# solar-pmic.net
KiCad netlist of a schematic drawn in EAGLE
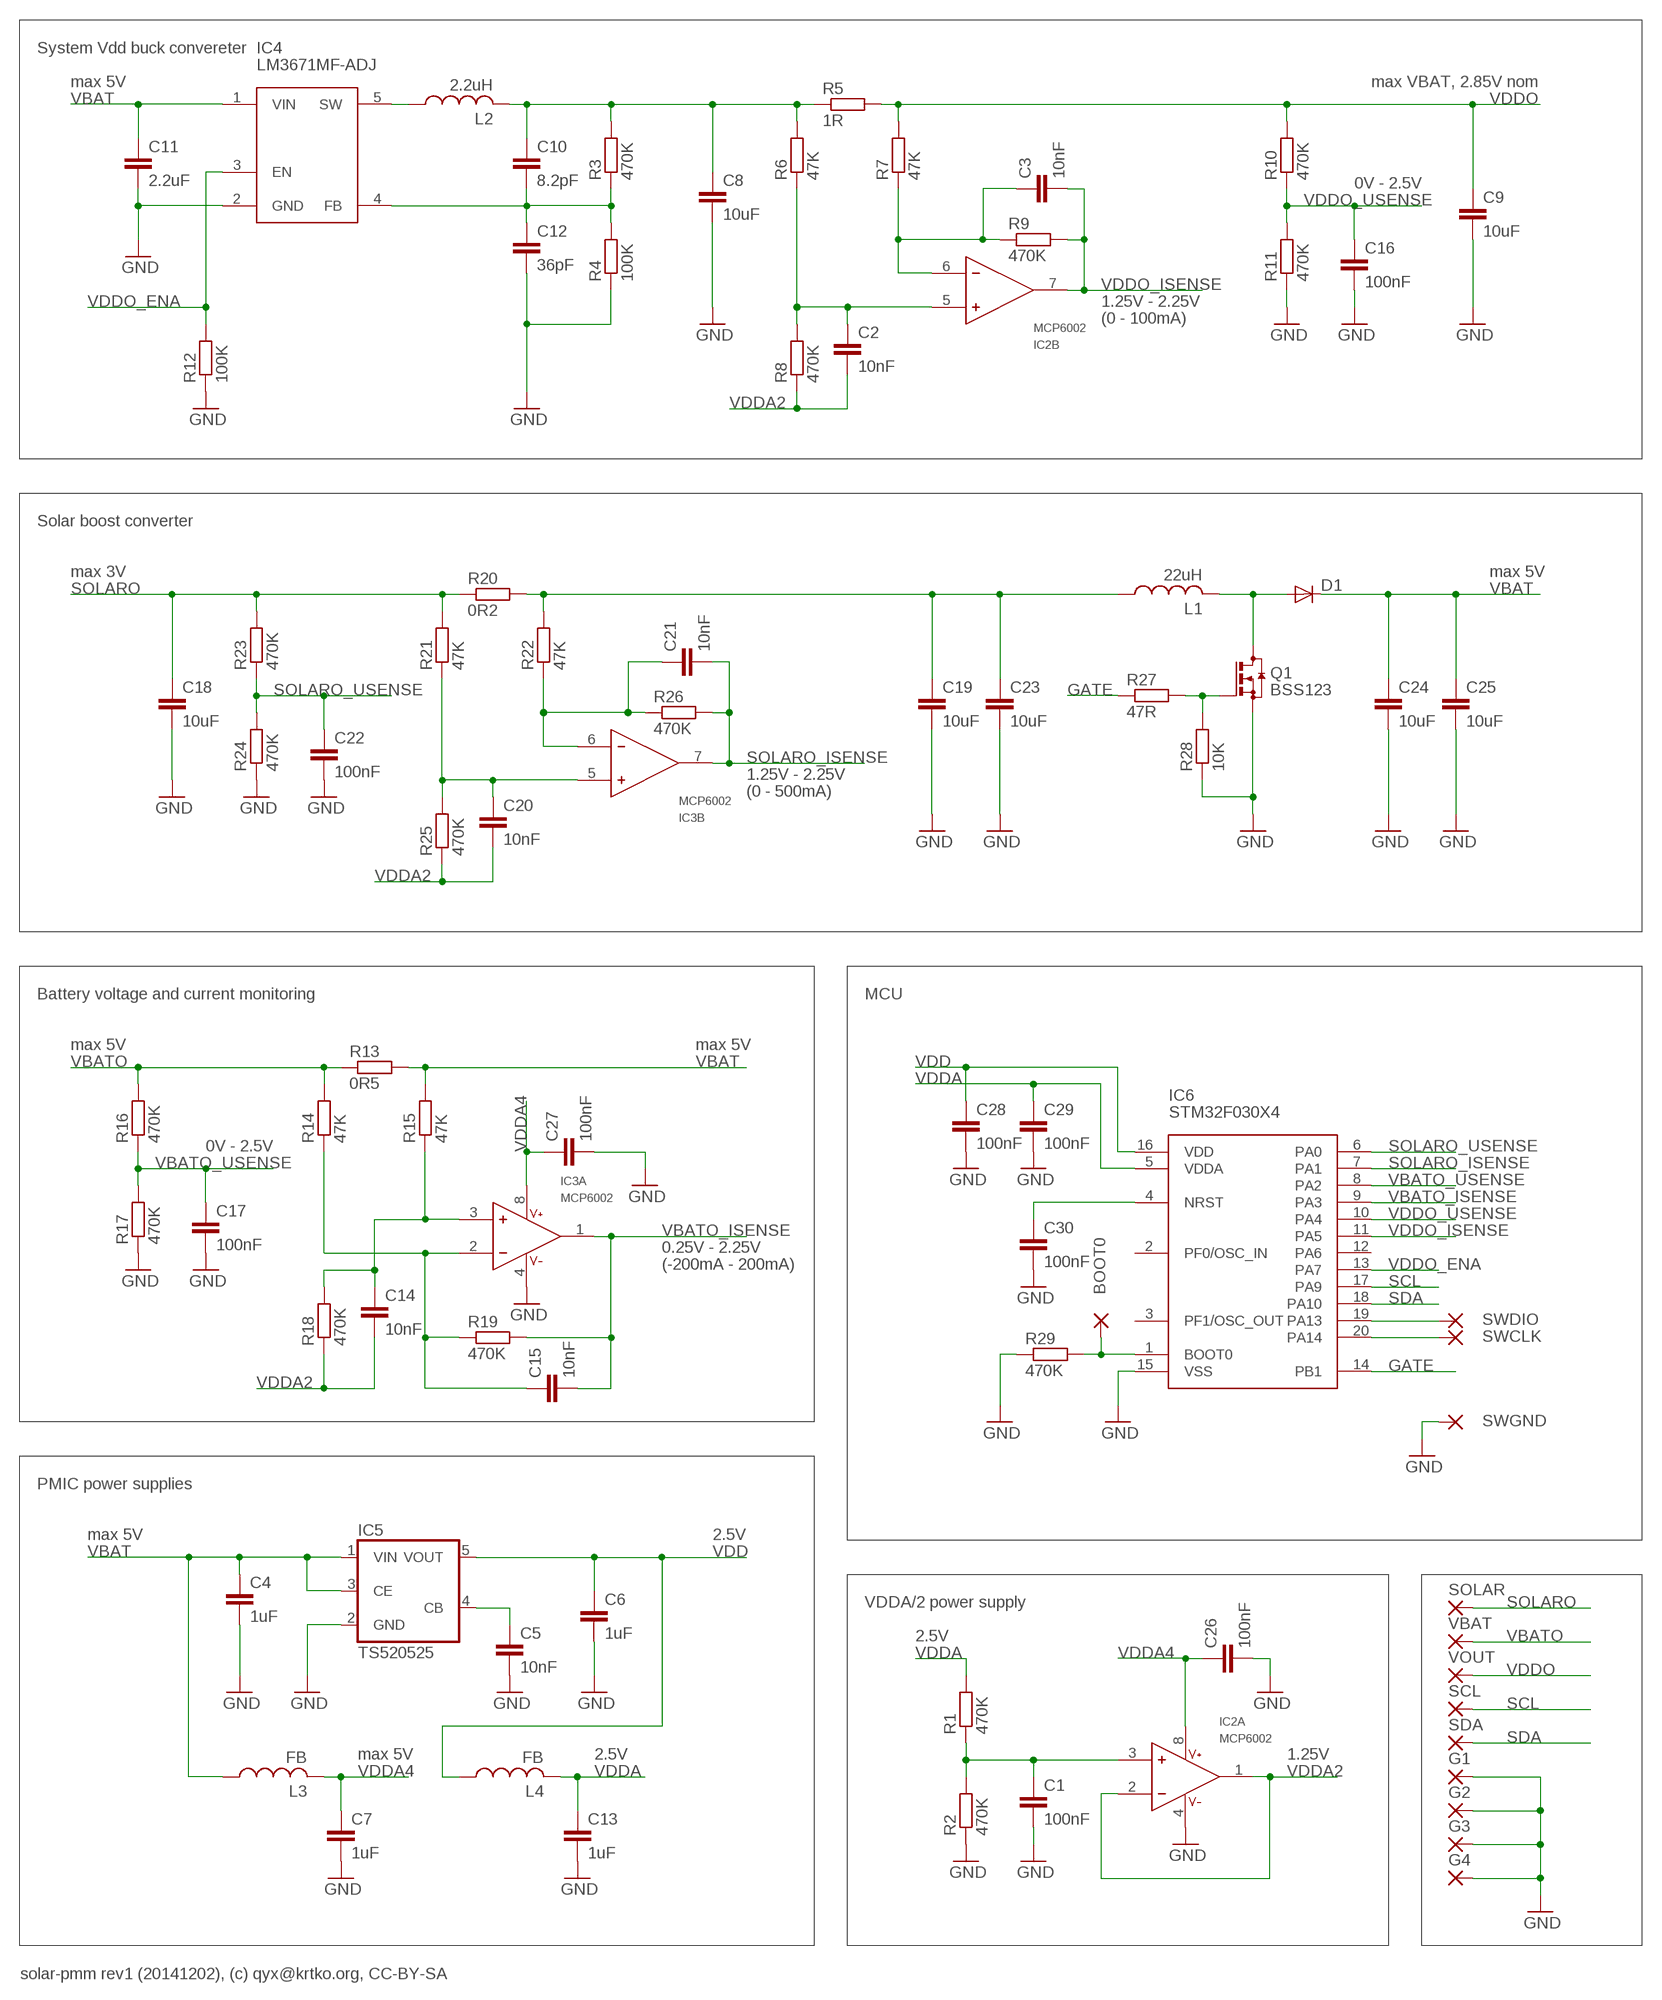
[diagram p0: schematic, sheet 1]

(export (version "E")
  (design (tool "Eeschema 10.0.6"))
  (components
    (comp (ref "BOOT0")
      (value "SMD2")
      (footprint "eagle-import:SMD1,27-2,54")
      (libsource (lib "eagle-import") (part "SMD2"))
    )
    (comp (ref "C1")
      (value "100nF")
      (footprint "eagle-import:C0603")
      (libsource (lib "eagle-import") (part "C-EUC0603"))
    )
    (comp (ref "C2")
      (value "10nF")
      (footprint "eagle-import:C0603")
      (libsource (lib "eagle-import") (part "C-EUC0603"))
    )
    (comp (ref "C3")
      (value "10nF")
      (footprint "eagle-import:C0603")
      (libsource (lib "eagle-import") (part "C-EUC0603"))
    )
    (comp (ref "C4")
      (value "1uF")
      (footprint "eagle-import:C0603")
      (libsource (lib "eagle-import") (part "C-EUC0603"))
    )
    (comp (ref "C5")
      (value "10nF")
      (footprint "eagle-import:C0603")
      (libsource (lib "eagle-import") (part "C-EUC0603"))
    )
    (comp (ref "C6")
      (value "1uF")
      (footprint "eagle-import:C0603")
      (libsource (lib "eagle-import") (part "C-EUC0603"))
    )
    (comp (ref "C7")
      (value "1uF")
      (footprint "eagle-import:C0603")
      (libsource (lib "eagle-import") (part "C-EUC0603"))
    )
    (comp (ref "C8")
      (value "10uF")
      (footprint "eagle-import:C0805")
      (libsource (lib "eagle-import") (part "C-EUC0805"))
    )
    (comp (ref "C9")
      (value "10uF")
      (footprint "eagle-import:C0805")
      (libsource (lib "eagle-import") (part "C-EUC0805"))
    )
    (comp (ref "C10")
      (value "8.2pF")
      (footprint "eagle-import:C0603")
      (libsource (lib "eagle-import") (part "C-EUC0603"))
    )
    (comp (ref "C11")
      (value "2.2uF")
      (footprint "eagle-import:C0805")
      (libsource (lib "eagle-import") (part "C-EUC0805"))
    )
    (comp (ref "C12")
      (value "36pF")
      (footprint "eagle-import:C0603")
      (libsource (lib "eagle-import") (part "C-EUC0603"))
    )
    (comp (ref "C13")
      (value "1uF")
      (footprint "eagle-import:C0603")
      (libsource (lib "eagle-import") (part "C-EUC0603"))
    )
    (comp (ref "C14")
      (value "10nF")
      (footprint "eagle-import:C0603")
      (libsource (lib "eagle-import") (part "C-EUC0603"))
    )
    (comp (ref "C15")
      (value "10nF")
      (footprint "eagle-import:C0603")
      (libsource (lib "eagle-import") (part "C-EUC0603"))
    )
    (comp (ref "C16")
      (value "100nF")
      (footprint "eagle-import:C0603")
      (libsource (lib "eagle-import") (part "C-EUC0603"))
    )
    (comp (ref "C17")
      (value "100nF")
      (footprint "eagle-import:C0603")
      (libsource (lib "eagle-import") (part "C-EUC0603"))
    )
    (comp (ref "C18")
      (value "10uF")
      (footprint "eagle-import:C0805")
      (libsource (lib "eagle-import") (part "C-EUC0805"))
    )
    (comp (ref "C19")
      (value "10uF")
      (footprint "eagle-import:C0805")
      (libsource (lib "eagle-import") (part "C-EUC0805"))
    )
    (comp (ref "C20")
      (value "10nF")
      (footprint "eagle-import:C0603")
      (libsource (lib "eagle-import") (part "C-EUC0603"))
    )
    (comp (ref "C21")
      (value "10nF")
      (footprint "eagle-import:C0603")
      (libsource (lib "eagle-import") (part "C-EUC0603"))
    )
    (comp (ref "C22")
      (value "100nF")
      (footprint "eagle-import:C0603")
      (libsource (lib "eagle-import") (part "C-EUC0603"))
    )
    (comp (ref "C23")
      (value "10uF")
      (footprint "eagle-import:C0805")
      (libsource (lib "eagle-import") (part "C-EUC0805"))
    )
    (comp (ref "C24")
      (value "10uF")
      (footprint "eagle-import:C0805")
      (libsource (lib "eagle-import") (part "C-EUC0805"))
    )
    (comp (ref "C25")
      (value "10uF")
      (footprint "eagle-import:C0805")
      (libsource (lib "eagle-import") (part "C-EUC0805"))
    )
    (comp (ref "C26")
      (value "100nF")
      (footprint "eagle-import:C0603")
      (libsource (lib "eagle-import") (part "C-EUC0603"))
    )
    (comp (ref "C27")
      (value "100nF")
      (footprint "eagle-import:C0603")
      (libsource (lib "eagle-import") (part "C-EUC0603"))
    )
    (comp (ref "C28")
      (value "100nF")
      (footprint "eagle-import:C0603")
      (libsource (lib "eagle-import") (part "C-EUC0603"))
    )
    (comp (ref "C29")
      (value "100nF")
      (footprint "eagle-import:C0603")
      (libsource (lib "eagle-import") (part "C-EUC0603"))
    )
    (comp (ref "C30")
      (value "100nF")
      (footprint "eagle-import:C0603")
      (libsource (lib "eagle-import") (part "C-EUC0603"))
    )
    (comp (ref "D1")
      (value "DIODE-MINIMELF")
      (footprint "eagle-import:MINIMELF")
      (libsource (lib "eagle-import") (part "DIODE-MINIMELF"))
    )
    (comp (ref "G1")
      (value "2,15/1,0")
      (footprint "eagle-import:2,15_1,0")
      (libsource (lib "eagle-import") (part "2,15/1,0"))
    )
    (comp (ref "G2")
      (value "2,15/1,0")
      (footprint "eagle-import:2,15_1,0")
      (libsource (lib "eagle-import") (part "2,15/1,0"))
    )
    (comp (ref "G3")
      (value "2,15/1,0")
      (footprint "eagle-import:2,15_1,0")
      (libsource (lib "eagle-import") (part "2,15/1,0"))
    )
    (comp (ref "G4")
      (value "2,15/1,0")
      (footprint "eagle-import:2,15_1,0")
      (libsource (lib "eagle-import") (part "2,15/1,0"))
    )
    (comp (ref "IC2")
      (value "MCP6002")
      (footprint "eagle-import:MSOP8")
      (libsource (lib "eagle-import") (part "LT6237CMS8"))
    )
    (comp (ref "IC3")
      (value "MCP6002")
      (footprint "eagle-import:MSOP8")
      (libsource (lib "eagle-import") (part "LT6237CMS8"))
    )
    (comp (ref "IC4")
      (value "LM3671MF-ADJ")
      (footprint "eagle-import:SOT23-5")
      (libsource (lib "eagle-import") (part "LM3671MF"))
    )
    (comp (ref "IC5")
      (value "TS520525")
      (footprint "eagle-import:SOT25")
      (libsource (lib "eagle-import") (part "TS520525"))
    )
    (comp (ref "IC6")
      (value "STM32F030X4")
      (footprint "eagle-import:TSSOP20_SO")
      (libsource (lib "eagle-import") (part "STM32F030X4"))
    )
    (comp (ref "L1")
      (value "22uH")
      (footprint "eagle-import:L3225M")
      (libsource (lib "eagle-import") (part "L-USL3225M"))
    )
    (comp (ref "L2")
      (value "2.2uH")
      (footprint "eagle-import:L3225M")
      (libsource (lib "eagle-import") (part "L-USL3225M"))
    )
    (comp (ref "L3")
      (value "FB")
      (footprint "eagle-import:L2012C")
      (libsource (lib "eagle-import") (part "L-USL2012C"))
    )
    (comp (ref "L4")
      (value "FB")
      (footprint "eagle-import:L2012C")
      (libsource (lib "eagle-import") (part "L-USL2012C"))
    )
    (comp (ref "Q1")
      (value "BSS123")
      (footprint "eagle-import:SOT23")
      (libsource (lib "eagle-import") (part "BSS123"))
    )
    (comp (ref "R1")
      (value "470K")
      (footprint "eagle-import:R0603")
      (libsource (lib "eagle-import") (part "R-EU_R0603"))
    )
    (comp (ref "R2")
      (value "470K")
      (footprint "eagle-import:R0603")
      (libsource (lib "eagle-import") (part "R-EU_R0603"))
    )
    (comp (ref "R3")
      (value "470K")
      (footprint "eagle-import:R0603")
      (libsource (lib "eagle-import") (part "R-EU_R0603"))
    )
    (comp (ref "R4")
      (value "100K")
      (footprint "eagle-import:R0603")
      (libsource (lib "eagle-import") (part "R-EU_R0603"))
    )
    (comp (ref "R5")
      (value "1R")
      (footprint "eagle-import:R0805")
      (libsource (lib "eagle-import") (part "R-EU_R0805"))
    )
    (comp (ref "R6")
      (value "47K")
      (footprint "eagle-import:R0603")
      (libsource (lib "eagle-import") (part "R-EU_R0603"))
    )
    (comp (ref "R7")
      (value "47K")
      (footprint "eagle-import:R0603")
      (libsource (lib "eagle-import") (part "R-EU_R0603"))
    )
    (comp (ref "R8")
      (value "470K")
      (footprint "eagle-import:R0603")
      (libsource (lib "eagle-import") (part "R-EU_R0603"))
    )
    (comp (ref "R9")
      (value "470K")
      (footprint "eagle-import:R0603")
      (libsource (lib "eagle-import") (part "R-EU_R0603"))
    )
    (comp (ref "R10")
      (value "470K")
      (footprint "eagle-import:R0603")
      (libsource (lib "eagle-import") (part "R-EU_R0603"))
    )
    (comp (ref "R11")
      (value "470K")
      (footprint "eagle-import:R0603")
      (libsource (lib "eagle-import") (part "R-EU_R0603"))
    )
    (comp (ref "R12")
      (value "100K")
      (footprint "eagle-import:R0603")
      (libsource (lib "eagle-import") (part "R-EU_R0603"))
    )
    (comp (ref "R13")
      (value "0R5")
      (footprint "eagle-import:R0805")
      (libsource (lib "eagle-import") (part "R-EU_R0805"))
    )
    (comp (ref "R14")
      (value "47K")
      (footprint "eagle-import:R0603")
      (libsource (lib "eagle-import") (part "R-EU_R0603"))
    )
    (comp (ref "R15")
      (value "47K")
      (footprint "eagle-import:R0603")
      (libsource (lib "eagle-import") (part "R-EU_R0603"))
    )
    (comp (ref "R16")
      (value "470K")
      (footprint "eagle-import:R0603")
      (libsource (lib "eagle-import") (part "R-EU_R0603"))
    )
    (comp (ref "R17")
      (value "470K")
      (footprint "eagle-import:R0603")
      (libsource (lib "eagle-import") (part "R-EU_R0603"))
    )
    (comp (ref "R18")
      (value "470K")
      (footprint "eagle-import:R0603")
      (libsource (lib "eagle-import") (part "R-EU_R0603"))
    )
    (comp (ref "R19")
      (value "470K")
      (footprint "eagle-import:R0603")
      (libsource (lib "eagle-import") (part "R-EU_R0603"))
    )
    (comp (ref "R20")
      (value "0R2")
      (footprint "eagle-import:R0805")
      (libsource (lib "eagle-import") (part "R-EU_R0805"))
    )
    (comp (ref "R21")
      (value "47K")
      (footprint "eagle-import:R0603")
      (libsource (lib "eagle-import") (part "R-EU_R0603"))
    )
    (comp (ref "R22")
      (value "47K")
      (footprint "eagle-import:R0603")
      (libsource (lib "eagle-import") (part "R-EU_R0603"))
    )
    (comp (ref "R23")
      (value "470K")
      (footprint "eagle-import:R0603")
      (libsource (lib "eagle-import") (part "R-EU_R0603"))
    )
    (comp (ref "R24")
      (value "470K")
      (footprint "eagle-import:R0603")
      (libsource (lib "eagle-import") (part "R-EU_R0603"))
    )
    (comp (ref "R25")
      (value "470K")
      (footprint "eagle-import:R0603")
      (libsource (lib "eagle-import") (part "R-EU_R0603"))
    )
    (comp (ref "R26")
      (value "470K")
      (footprint "eagle-import:R0603")
      (libsource (lib "eagle-import") (part "R-EU_R0603"))
    )
    (comp (ref "R27")
      (value "47R")
      (footprint "eagle-import:R0603")
      (libsource (lib "eagle-import") (part "R-EU_R0603"))
    )
    (comp (ref "R28")
      (value "10K")
      (footprint "eagle-import:R0603")
      (libsource (lib "eagle-import") (part "R-EU_R0603"))
    )
    (comp (ref "R29")
      (value "470K")
      (footprint "eagle-import:R0603")
      (libsource (lib "eagle-import") (part "R-EU_R0603"))
    )
    (comp (ref "SCL")
      (value "2,15/1,0")
      (footprint "eagle-import:2,15_1,0")
      (libsource (lib "eagle-import") (part "2,15/1,0"))
    )
    (comp (ref "SDA")
      (value "2,15/1,0")
      (footprint "eagle-import:2,15_1,0")
      (libsource (lib "eagle-import") (part "2,15/1,0"))
    )
    (comp (ref "SOLAR")
      (value "2,15/1,0")
      (footprint "eagle-import:2,15_1,0")
      (libsource (lib "eagle-import") (part "2,15/1,0"))
    )
    (comp (ref "SWCLK")
      (value "SMD2")
      (footprint "eagle-import:SMD1,27-2,54")
      (libsource (lib "eagle-import") (part "SMD2"))
    )
    (comp (ref "SWDIO")
      (value "SMD2")
      (footprint "eagle-import:SMD1,27-2,54")
      (libsource (lib "eagle-import") (part "SMD2"))
    )
    (comp (ref "SWGND")
      (value "SMD2")
      (footprint "eagle-import:SMD1,27-2,54")
      (libsource (lib "eagle-import") (part "SMD2"))
    )
    (comp (ref "VBAT")
      (value "2,15/1,0")
      (footprint "eagle-import:2,15_1,0")
      (libsource (lib "eagle-import") (part "2,15/1,0"))
    )
    (comp (ref "VOUT")
      (value "2,15/1,0")
      (footprint "eagle-import:2,15_1,0")
      (libsource (lib "eagle-import") (part "2,15/1,0"))
    )
  )
  (nets
    (net (code "1") (name "/GATE") (class "Default")
      (node (ref "IC6") (pin "14") (pinfunction "PB1_14") (pintype "bidirectional"))
      (node (ref "R27") (pin "1") (pinfunction "1_1") (pintype "passive"))
    )
    (net (code "2") (name "/SCL") (class "Default")
      (node (ref "IC6") (pin "17") (pinfunction "PA9_17") (pintype "bidirectional"))
      (node (ref "SCL") (pin "1") (pinfunction "P_1") (pintype "passive"))
    )
    (net (code "3") (name "/SDA") (class "Default")
      (node (ref "IC6") (pin "18") (pinfunction "PA10_18") (pintype "bidirectional"))
      (node (ref "SDA") (pin "1") (pinfunction "P_1") (pintype "passive"))
    )
    (net (code "4") (name "/SOLARO") (class "Default")
      (node (ref "C18") (pin "1") (pinfunction "1_1") (pintype "passive"))
      (node (ref "R20") (pin "1") (pinfunction "1_1") (pintype "passive"))
      (node (ref "R21") (pin "2") (pinfunction "2_2") (pintype "passive"))
      (node (ref "R23") (pin "2") (pinfunction "2_2") (pintype "passive"))
      (node (ref "SOLAR") (pin "1") (pinfunction "P_1") (pintype "passive"))
    )
    (net (code "5") (name "/SOLARO_ISENSE") (class "Default")
      (node (ref "C21") (pin "2") (pinfunction "2_2") (pintype "passive"))
      (node (ref "IC3") (pin "7") (pinfunction "OUT_7") (pintype "bidirectional"))
      (node (ref "IC6") (pin "7") (pinfunction "PA1_7") (pintype "bidirectional"))
      (node (ref "R26") (pin "2") (pinfunction "2_2") (pintype "passive"))
    )
    (net (code "6") (name "/SOLARO_USENSE") (class "Default")
      (node (ref "C22") (pin "1") (pinfunction "1_1") (pintype "passive"))
      (node (ref "IC6") (pin "6") (pinfunction "PA0_6") (pintype "bidirectional"))
      (node (ref "R23") (pin "1") (pinfunction "1_1") (pintype "passive"))
      (node (ref "R24") (pin "2") (pinfunction "2_2") (pintype "passive"))
    )
    (net (code "7") (name "/VBAT") (class "Default")
      (node (ref "C11") (pin "1") (pinfunction "1_1") (pintype "passive"))
      (node (ref "C24") (pin "1") (pinfunction "1_1") (pintype "passive"))
      (node (ref "C25") (pin "1") (pinfunction "1_1") (pintype "passive"))
      (node (ref "C4") (pin "1") (pinfunction "1_1") (pintype "passive"))
      (node (ref "D1") (pin "C") (pinfunction "C_C") (pintype "passive"))
      (node (ref "IC4") (pin "1") (pinfunction "VIN_1") (pintype "bidirectional"))
      (node (ref "IC5") (pin "1") (pinfunction "VIN_1") (pintype "input"))
      (node (ref "IC5") (pin "3") (pinfunction "CE_3") (pintype "input"))
      (node (ref "L3") (pin "1") (pinfunction "1_1") (pintype "passive"))
      (node (ref "R13") (pin "2") (pinfunction "2_2") (pintype "passive"))
      (node (ref "R15") (pin "2") (pinfunction "2_2") (pintype "passive"))
    )
    (net (code "8") (name "/VBATO") (class "Default")
      (node (ref "R13") (pin "1") (pinfunction "1_1") (pintype "passive"))
      (node (ref "R14") (pin "2") (pinfunction "2_2") (pintype "passive"))
      (node (ref "R16") (pin "2") (pinfunction "2_2") (pintype "passive"))
      (node (ref "VBAT") (pin "1") (pinfunction "P_1") (pintype "passive"))
    )
    (net (code "9") (name "/VBATO_ISENSE") (class "Default")
      (node (ref "C15") (pin "2") (pinfunction "2_2") (pintype "passive"))
      (node (ref "IC3") (pin "1") (pinfunction "OUT_1") (pintype "bidirectional"))
      (node (ref "IC6") (pin "9") (pinfunction "PA3_9") (pintype "bidirectional"))
      (node (ref "R19") (pin "2") (pinfunction "2_2") (pintype "passive"))
    )
    (net (code "10") (name "/VBATO_USENSE") (class "Default")
      (node (ref "C17") (pin "1") (pinfunction "1_1") (pintype "passive"))
      (node (ref "IC6") (pin "8") (pinfunction "PA2_8") (pintype "bidirectional"))
      (node (ref "R16") (pin "1") (pinfunction "1_1") (pintype "passive"))
      (node (ref "R17") (pin "2") (pinfunction "2_2") (pintype "passive"))
    )
    (net (code "11") (name "/VDD") (class "Default")
      (node (ref "C28") (pin "1") (pinfunction "1_1") (pintype "passive"))
      (node (ref "C6") (pin "1") (pinfunction "1_1") (pintype "passive"))
      (node (ref "IC5") (pin "5") (pinfunction "VOUT_5") (pintype "passive"))
      (node (ref "IC6") (pin "16") (pinfunction "VDD_16") (pintype "bidirectional"))
      (node (ref "L4") (pin "1") (pinfunction "1_1") (pintype "passive"))
    )
    (net (code "12") (name "/VDDA") (class "Default")
      (node (ref "C13") (pin "1") (pinfunction "1_1") (pintype "passive"))
      (node (ref "C29") (pin "1") (pinfunction "1_1") (pintype "passive"))
      (node (ref "IC6") (pin "5") (pinfunction "VDDA_5") (pintype "bidirectional"))
      (node (ref "L4") (pin "2") (pinfunction "2_2") (pintype "passive"))
      (node (ref "R1") (pin "2") (pinfunction "2_2") (pintype "passive"))
    )
    (net (code "13") (name "/VDDA2") (class "Default")
      (node (ref "C14") (pin "2") (pinfunction "2_2") (pintype "passive"))
      (node (ref "C2") (pin "2") (pinfunction "2_2") (pintype "passive"))
      (node (ref "C20") (pin "2") (pinfunction "2_2") (pintype "passive"))
      (node (ref "IC2") (pin "1") (pinfunction "OUT_1") (pintype "bidirectional"))
      (node (ref "IC2") (pin "2") (pinfunction "IN-_2") (pintype "bidirectional"))
      (node (ref "R18") (pin "1") (pinfunction "1_1") (pintype "passive"))
      (node (ref "R25") (pin "1") (pinfunction "1_1") (pintype "passive"))
      (node (ref "R8") (pin "1") (pinfunction "1_1") (pintype "passive"))
    )
    (net (code "14") (name "/VDDA4") (class "Default")
      (node (ref "C26") (pin "1") (pinfunction "1_1") (pintype "passive"))
      (node (ref "C27") (pin "1") (pinfunction "1_1") (pintype "passive"))
      (node (ref "C7") (pin "1") (pinfunction "1_1") (pintype "passive"))
      (node (ref "IC2") (pin "8") (pinfunction "V+_8") (pintype "bidirectional"))
      (node (ref "IC3") (pin "8") (pinfunction "V+_8") (pintype "bidirectional"))
      (node (ref "L3") (pin "2") (pinfunction "2_2") (pintype "passive"))
    )
    (net (code "15") (name "/VDDO") (class "Default")
      (node (ref "C9") (pin "1") (pinfunction "1_1") (pintype "passive"))
      (node (ref "R10") (pin "2") (pinfunction "2_2") (pintype "passive"))
      (node (ref "R5") (pin "2") (pinfunction "2_2") (pintype "passive"))
      (node (ref "R7") (pin "2") (pinfunction "2_2") (pintype "passive"))
      (node (ref "VOUT") (pin "1") (pinfunction "P_1") (pintype "passive"))
    )
    (net (code "16") (name "/VDDO_ENA") (class "Default")
      (node (ref "IC4") (pin "3") (pinfunction "EN_3") (pintype "bidirectional"))
      (node (ref "IC6") (pin "13") (pinfunction "PA7_13") (pintype "bidirectional"))
      (node (ref "R12") (pin "2") (pinfunction "2_2") (pintype "passive"))
    )
    (net (code "17") (name "/VDDO_ISENSE") (class "Default")
      (node (ref "C3") (pin "2") (pinfunction "2_2") (pintype "passive"))
      (node (ref "IC2") (pin "7") (pinfunction "OUT_7") (pintype "bidirectional"))
      (node (ref "IC6") (pin "11") (pinfunction "PA5_11") (pintype "bidirectional"))
      (node (ref "R9") (pin "2") (pinfunction "2_2") (pintype "passive"))
    )
    (net (code "18") (name "/VDDO_USENSE") (class "Default")
      (node (ref "C16") (pin "1") (pinfunction "1_1") (pintype "passive"))
      (node (ref "IC6") (pin "10") (pinfunction "PA4_10") (pintype "bidirectional"))
      (node (ref "R10") (pin "1") (pinfunction "1_1") (pintype "passive"))
      (node (ref "R11") (pin "2") (pinfunction "2_2") (pintype "passive"))
    )
    (net (code "19") (name "GND") (class "Default")
      (node (ref "C1") (pin "2") (pinfunction "2_2") (pintype "passive"))
      (node (ref "C11") (pin "2") (pinfunction "2_2") (pintype "passive"))
      (node (ref "C12") (pin "2") (pinfunction "2_2") (pintype "passive"))
      (node (ref "C13") (pin "2") (pinfunction "2_2") (pintype "passive"))
      (node (ref "C16") (pin "2") (pinfunction "2_2") (pintype "passive"))
      (node (ref "C17") (pin "2") (pinfunction "2_2") (pintype "passive"))
      (node (ref "C18") (pin "2") (pinfunction "2_2") (pintype "passive"))
      (node (ref "C19") (pin "2") (pinfunction "2_2") (pintype "passive"))
      (node (ref "C22") (pin "2") (pinfunction "2_2") (pintype "passive"))
      (node (ref "C23") (pin "2") (pinfunction "2_2") (pintype "passive"))
      (node (ref "C24") (pin "2") (pinfunction "2_2") (pintype "passive"))
      (node (ref "C25") (pin "2") (pinfunction "2_2") (pintype "passive"))
      (node (ref "C26") (pin "2") (pinfunction "2_2") (pintype "passive"))
      (node (ref "C27") (pin "2") (pinfunction "2_2") (pintype "passive"))
      (node (ref "C28") (pin "2") (pinfunction "2_2") (pintype "passive"))
      (node (ref "C29") (pin "2") (pinfunction "2_2") (pintype "passive"))
      (node (ref "C30") (pin "2") (pinfunction "2_2") (pintype "passive"))
      (node (ref "C4") (pin "2") (pinfunction "2_2") (pintype "passive"))
      (node (ref "C5") (pin "2") (pinfunction "2_2") (pintype "passive"))
      (node (ref "C6") (pin "2") (pinfunction "2_2") (pintype "passive"))
      (node (ref "C7") (pin "2") (pinfunction "2_2") (pintype "passive"))
      (node (ref "C8") (pin "2") (pinfunction "2_2") (pintype "passive"))
      (node (ref "C9") (pin "2") (pinfunction "2_2") (pintype "passive"))
      (node (ref "G1") (pin "1") (pinfunction "P_1") (pintype "passive"))
      (node (ref "G2") (pin "1") (pinfunction "P_1") (pintype "passive"))
      (node (ref "G3") (pin "1") (pinfunction "P_1") (pintype "passive"))
      (node (ref "G4") (pin "1") (pinfunction "P_1") (pintype "passive"))
      (node (ref "IC2") (pin "4") (pinfunction "V-_4") (pintype "bidirectional"))
      (node (ref "IC3") (pin "4") (pinfunction "V-_4") (pintype "bidirectional"))
      (node (ref "IC4") (pin "2") (pinfunction "GND_2") (pintype "bidirectional"))
      (node (ref "IC5") (pin "2") (pinfunction "GND_2") (pintype "passive"))
      (node (ref "IC6") (pin "15") (pinfunction "VSS_15") (pintype "bidirectional"))
      (node (ref "Q1") (pin "2") (pinfunction "S_2") (pintype "passive"))
      (node (ref "R11") (pin "1") (pinfunction "1_1") (pintype "passive"))
      (node (ref "R12") (pin "1") (pinfunction "1_1") (pintype "passive"))
      (node (ref "R17") (pin "1") (pinfunction "1_1") (pintype "passive"))
      (node (ref "R2") (pin "1") (pinfunction "1_1") (pintype "passive"))
      (node (ref "R24") (pin "1") (pinfunction "1_1") (pintype "passive"))
      (node (ref "R28") (pin "1") (pinfunction "1_1") (pintype "passive"))
      (node (ref "R29") (pin "1") (pinfunction "1_1") (pintype "passive"))
      (node (ref "R4") (pin "1") (pinfunction "1_1") (pintype "passive"))
      (node (ref "SWGND") (pin "1") (pinfunction "P_1") (pintype "passive"))
    )
    (net (code "20") (name "Net-(BOOT0-P)") (class "Default")
      (node (ref "BOOT0") (pin "1") (pinfunction "P_1") (pintype "passive"))
      (node (ref "IC6") (pin "1") (pinfunction "BOOT0_1") (pintype "bidirectional"))
      (node (ref "R29") (pin "2") (pinfunction "2_2") (pintype "passive"))
    )
    (net (code "21") (name "Net-(C10-Pad1)") (class "Default")
      (node (ref "C10") (pin "1") (pinfunction "1_1") (pintype "passive"))
      (node (ref "C8") (pin "1") (pinfunction "1_1") (pintype "passive"))
      (node (ref "L2") (pin "2") (pinfunction "2_2") (pintype "passive"))
      (node (ref "R3") (pin "2") (pinfunction "2_2") (pintype "passive"))
      (node (ref "R5") (pin "1") (pinfunction "1_1") (pintype "passive"))
      (node (ref "R6") (pin "2") (pinfunction "2_2") (pintype "passive"))
    )
    (net (code "22") (name "Net-(C19-Pad1)") (class "Default")
      (node (ref "C19") (pin "1") (pinfunction "1_1") (pintype "passive"))
      (node (ref "C23") (pin "1") (pinfunction "1_1") (pintype "passive"))
      (node (ref "L1") (pin "1") (pinfunction "1_1") (pintype "passive"))
      (node (ref "R20") (pin "2") (pinfunction "2_2") (pintype "passive"))
      (node (ref "R22") (pin "2") (pinfunction "2_2") (pintype "passive"))
    )
    (net (code "23") (name "Net-(IC2A-IN+)") (class "Default")
      (node (ref "C1") (pin "1") (pinfunction "1_1") (pintype "passive"))
      (node (ref "IC2") (pin "3") (pinfunction "IN+_3") (pintype "bidirectional"))
      (node (ref "R1") (pin "1") (pinfunction "1_1") (pintype "passive"))
      (node (ref "R2") (pin "2") (pinfunction "2_2") (pintype "passive"))
    )
    (net (code "24") (name "Net-(IC2B-IN+)") (class "Default")
      (node (ref "C2") (pin "1") (pinfunction "1_1") (pintype "passive"))
      (node (ref "IC2") (pin "5") (pinfunction "IN+_5") (pintype "bidirectional"))
      (node (ref "R6") (pin "1") (pinfunction "1_1") (pintype "passive"))
      (node (ref "R8") (pin "2") (pinfunction "2_2") (pintype "passive"))
    )
    (net (code "25") (name "Net-(IC2B-IN-)") (class "Default")
      (node (ref "C3") (pin "1") (pinfunction "1_1") (pintype "passive"))
      (node (ref "IC2") (pin "6") (pinfunction "IN-_6") (pintype "bidirectional"))
      (node (ref "R7") (pin "1") (pinfunction "1_1") (pintype "passive"))
      (node (ref "R9") (pin "1") (pinfunction "1_1") (pintype "passive"))
    )
    (net (code "26") (name "Net-(IC3A-IN+)") (class "Default")
      (node (ref "C14") (pin "1") (pinfunction "1_1") (pintype "passive"))
      (node (ref "IC3") (pin "3") (pinfunction "IN+_3") (pintype "bidirectional"))
      (node (ref "R15") (pin "1") (pinfunction "1_1") (pintype "passive"))
      (node (ref "R18") (pin "2") (pinfunction "2_2") (pintype "passive"))
    )
    (net (code "27") (name "Net-(IC3A-IN-)") (class "Default")
      (node (ref "C15") (pin "1") (pinfunction "1_1") (pintype "passive"))
      (node (ref "IC3") (pin "2") (pinfunction "IN-_2") (pintype "bidirectional"))
      (node (ref "R14") (pin "1") (pinfunction "1_1") (pintype "passive"))
      (node (ref "R19") (pin "1") (pinfunction "1_1") (pintype "passive"))
    )
    (net (code "28") (name "Net-(IC3B-IN+)") (class "Default")
      (node (ref "C20") (pin "1") (pinfunction "1_1") (pintype "passive"))
      (node (ref "IC3") (pin "5") (pinfunction "IN+_5") (pintype "bidirectional"))
      (node (ref "R21") (pin "1") (pinfunction "1_1") (pintype "passive"))
      (node (ref "R25") (pin "2") (pinfunction "2_2") (pintype "passive"))
    )
    (net (code "29") (name "Net-(IC3B-IN-)") (class "Default")
      (node (ref "C21") (pin "1") (pinfunction "1_1") (pintype "passive"))
      (node (ref "IC3") (pin "6") (pinfunction "IN-_6") (pintype "bidirectional"))
      (node (ref "R22") (pin "1") (pinfunction "1_1") (pintype "passive"))
      (node (ref "R26") (pin "1") (pinfunction "1_1") (pintype "passive"))
    )
    (net (code "30") (name "Net-(IC4-FB)") (class "Default")
      (node (ref "C10") (pin "2") (pinfunction "2_2") (pintype "passive"))
      (node (ref "C12") (pin "1") (pinfunction "1_1") (pintype "passive"))
      (node (ref "IC4") (pin "4") (pinfunction "FB_4") (pintype "bidirectional"))
      (node (ref "R3") (pin "1") (pinfunction "1_1") (pintype "passive"))
      (node (ref "R4") (pin "2") (pinfunction "2_2") (pintype "passive"))
    )
    (net (code "31") (name "Net-(IC4-SW)") (class "Default")
      (node (ref "IC4") (pin "5") (pinfunction "SW_5") (pintype "bidirectional"))
      (node (ref "L2") (pin "1") (pinfunction "1_1") (pintype "passive"))
    )
    (net (code "32") (name "Net-(IC5-CB)") (class "Default")
      (node (ref "C5") (pin "1") (pinfunction "1_1") (pintype "passive"))
      (node (ref "IC5") (pin "4") (pinfunction "CB_4") (pintype "input"))
    )
    (net (code "33") (name "Net-(IC6-NRST)") (class "Default")
      (node (ref "C30") (pin "1") (pinfunction "1_1") (pintype "passive"))
      (node (ref "IC6") (pin "4") (pinfunction "NRST_4") (pintype "bidirectional"))
    )
    (net (code "34") (name "Net-(IC6-PA13)") (class "Default")
      (node (ref "IC6") (pin "19") (pinfunction "PA13_19") (pintype "bidirectional"))
      (node (ref "SWDIO") (pin "1") (pinfunction "P_1") (pintype "passive"))
    )
    (net (code "35") (name "Net-(IC6-PA14)") (class "Default")
      (node (ref "IC6") (pin "20") (pinfunction "PA14_20") (pintype "bidirectional"))
      (node (ref "SWCLK") (pin "1") (pinfunction "P_1") (pintype "passive"))
    )
    (net (code "36") (name "Net-(Q1-D)") (class "Default")
      (node (ref "D1") (pin "A") (pinfunction "A_A") (pintype "passive"))
      (node (ref "L1") (pin "2") (pinfunction "2_2") (pintype "passive"))
      (node (ref "Q1") (pin "3") (pinfunction "D_3") (pintype "passive"))
    )
    (net (code "37") (name "Net-(Q1-G)") (class "Default")
      (node (ref "Q1") (pin "1") (pinfunction "G_1") (pintype "passive"))
      (node (ref "R27") (pin "2") (pinfunction "2_2") (pintype "passive"))
      (node (ref "R28") (pin "2") (pinfunction "2_2") (pintype "passive"))
    )
    (net (code "38") (name "unconnected-(IC6-PA6-Pad12)") (class "Default")
      (node (ref "IC6") (pin "12") (pinfunction "PA6_12") (pintype "bidirectional"))
    )
    (net (code "39") (name "unconnected-(IC6-PF0{slash}OSC_IN-Pad2)") (class "Default")
      (node (ref "IC6") (pin "2") (pinfunction "PF0/OSC_IN_2") (pintype "bidirectional"))
    )
    (net (code "40") (name "unconnected-(IC6-PF1{slash}OSC_OUT-Pad3)") (class "Default")
      (node (ref "IC6") (pin "3") (pinfunction "PF1/OSC_OUT_3") (pintype "bidirectional"))
    )
  )
)
